# zxuno.net
KiCad netlist of a schematic drawn in Altium Designer
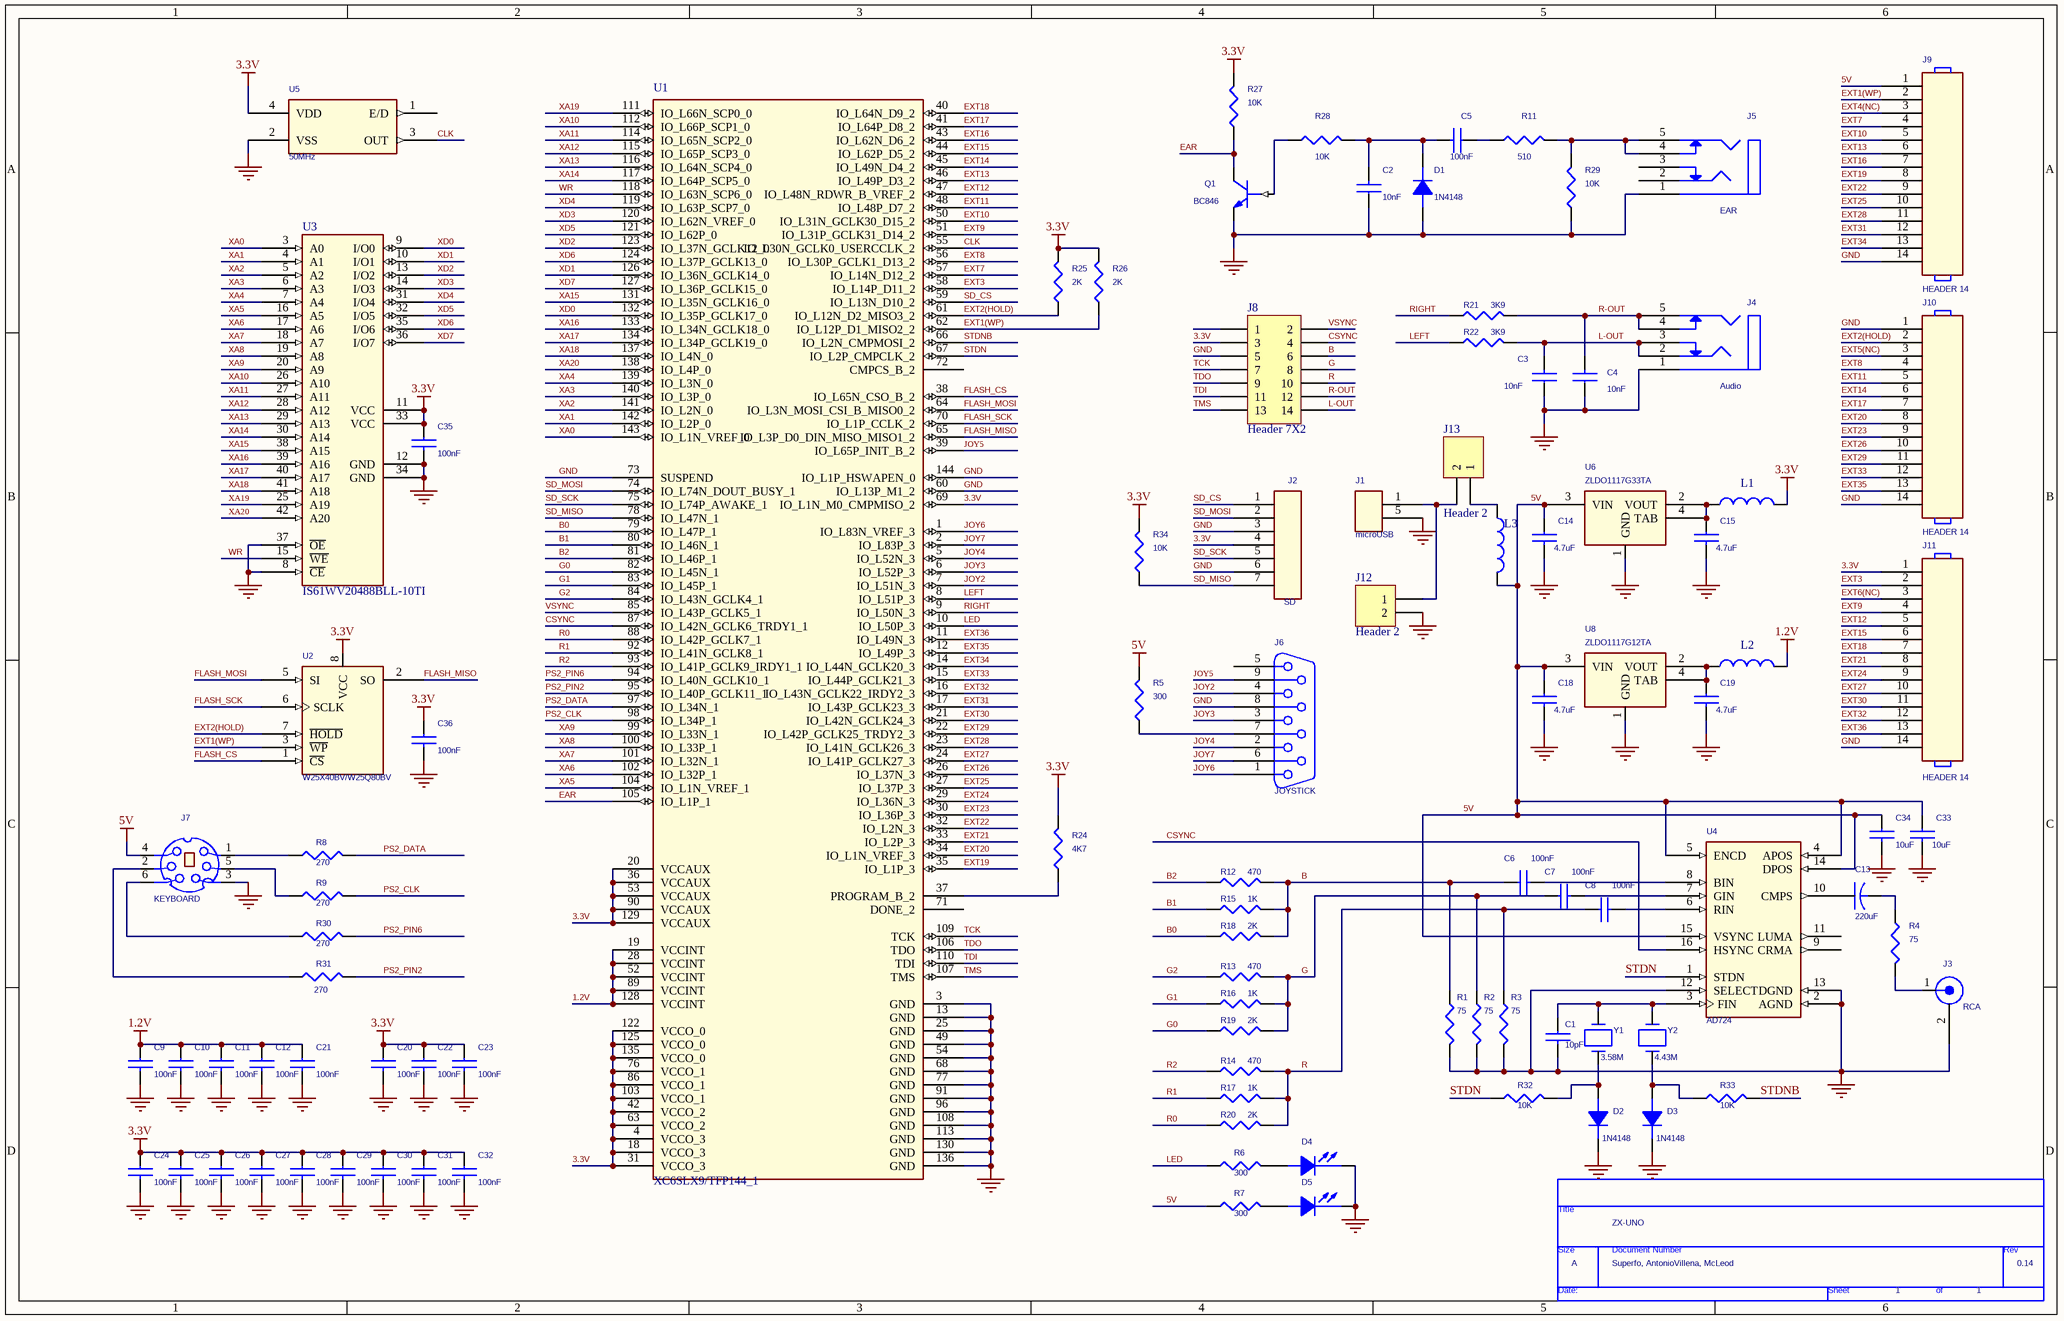
[diagram p0: zxuno.SchDoc]

(export (version "E")
  (design (tool "Eeschema 10.0.6"))
  (components
    (comp (ref "*")
      (value "TitleBlock0")
      (fields
        (field (name "PAGE COUNT") "1")
        (field (name "PAGE NUMBER") "1")
        (field (name "PAGE SIZE") "A")
        (field (name "TITLE") "ZX-UNO")
        (field (name "REVCODE") "0.14")
        (field (name "DOC") "Superfo, AntonioVillena, McLeod")
      )
      (libsource (lib "*") (part "TitleBlock0"))
    )
    (comp (ref "C1") (value "10pF") (libsource (lib "*") (part "CAP NP_Dup1")))
    (comp (ref "C2") (value "10nF") (libsource (lib "*") (part "CAP NP_Dup1")))
    (comp (ref "C3") (value "10nF") (libsource (lib "*") (part "CAP NP_Dup1")))
    (comp (ref "C4") (value "10nF") (libsource (lib "*") (part "CAP NP_Dup1")))
    (comp (ref "C5") (value "100nF") (libsource (lib "*") (part "CAP NP_Dup1")))
    (comp (ref "C6") (value "100nF") (libsource (lib "*") (part "CAP NP_Dup1")))
    (comp (ref "C7") (value "100nF") (libsource (lib "*") (part "CAP NP_Dup1")))
    (comp (ref "C8") (value "100nF") (libsource (lib "*") (part "CAP NP_Dup1")))
    (comp (ref "C9") (value "100nF") (libsource (lib "*") (part "CAP NP")))
    (comp (ref "C10") (value "100nF") (libsource (lib "*") (part "CAP NP")))
    (comp (ref "C11") (value "100nF") (libsource (lib "*") (part "CAP NP")))
    (comp (ref "C12") (value "100nF") (libsource (lib "*") (part "CAP NP")))
    (comp (ref "C13") (value "220uF") (libsource (lib "*") (part "CAP")))
    (comp (ref "C14") (value "4.7uF") (libsource (lib "*") (part "CAP NP")))
    (comp (ref "C15") (value "4.7uF") (libsource (lib "*") (part "CAP NP")))
    (comp (ref "C18") (value "4.7uF") (libsource (lib "*") (part "CAP NP")))
    (comp (ref "C19") (value "4.7uF") (libsource (lib "*") (part "CAP NP")))
    (comp (ref "C20") (value "100nF") (libsource (lib "*") (part "CAP NP")))
    (comp (ref "C21") (value "100nF") (libsource (lib "*") (part "CAP NP")))
    (comp (ref "C22") (value "100nF") (libsource (lib "*") (part "CAP NP")))
    (comp (ref "C23") (value "100nF") (libsource (lib "*") (part "CAP NP")))
    (comp (ref "C24") (value "100nF") (libsource (lib "*") (part "CAP NP")))
    (comp (ref "C25") (value "100nF") (libsource (lib "*") (part "CAP NP")))
    (comp (ref "C26") (value "100nF") (libsource (lib "*") (part "CAP NP")))
    (comp (ref "C27") (value "100nF") (libsource (lib "*") (part "CAP NP")))
    (comp (ref "C28") (value "100nF") (libsource (lib "*") (part "CAP NP")))
    (comp (ref "C29") (value "100nF") (libsource (lib "*") (part "CAP NP")))
    (comp (ref "C30") (value "100nF") (libsource (lib "*") (part "CAP NP")))
    (comp (ref "C31") (value "100nF") (libsource (lib "*") (part "CAP NP")))
    (comp (ref "C32") (value "100nF") (libsource (lib "*") (part "CAP NP")))
    (comp (ref "C33") (value "10uF") (libsource (lib "*") (part "CAP NP")))
    (comp (ref "C34") (value "10uF") (libsource (lib "*") (part "CAP NP")))
    (comp (ref "C35") (value "100nF") (libsource (lib "*") (part "CAP NP")))
    (comp (ref "C36") (value "100nF") (libsource (lib "*") (part "CAP NP")))
    (comp (ref "D1") (value "1N4148") (libsource (lib "*") (part "DIODE")))
    (comp (ref "D2") (value "1N4148") (libsource (lib "*") (part "DIODE")))
    (comp (ref "D3") (value "1N4148") (libsource (lib "*") (part "DIODE")))
    (comp (ref "D4") (value "LED") (libsource (lib "*") (part "LED")))
    (comp (ref "D5") (value "LED") (libsource (lib "*") (part "LED")))
    (comp (ref "J1") (value "microUSB") (libsource (lib "*") (part "CON2_0")))
    (comp (ref "J2") (value "SD") (libsource (lib "*") (part "CON7")))
    (comp (ref "J3") (value "RCA") (libsource (lib "*") (part "RCA JACK")))
    (comp (ref "J4")
      (value "Audio")
      (footprint "AUDIO JACK PSG01538 - duplicate")
      (libsource (lib "*") (part "PHONEJACK STEREO SW_0"))
    )
    (comp (ref "J5") (value "EAR") (libsource (lib "*") (part "PHONEJACK STEREO SW_0")))
    (comp (ref "J6") (value "JOYSTICK") (libsource (lib "*") (part "CONNECTOR DB9")))
    (comp (ref "J7") (value "KEYBOARD") (libsource (lib "*") (part "M-DIN_0")))
    (comp (ref "J8")
      (value "Header 7X2")
      (footprint "HDR2X7")
      (description "Header, 7-Pin, Dual row")
      (fields (field (name "PUBLISHER") "Altium Limited"))
      (libsource (lib "Miscellaneous Connectors") (part "Header 7X2"))
    )
    (comp (ref "J9") (value "HEADER 14") (libsource (lib "*") (part "HEADER 14")))
    (comp (ref "J10") (value "HEADER 14") (libsource (lib "*") (part "HEADER 14")))
    (comp (ref "J11") (value "HEADER 14") (libsource (lib "*") (part "HEADER 14")))
    (comp (ref "J12")
      (value "Header 2")
      (footprint "HDR1X2")
      (description "Header, 2-Pin")
      (fields (field (name "PUBLISHER") "Altium Limited"))
      (libsource (lib "Miscellaneous Connectors") (part "Header 2"))
    )
    (comp (ref "J13")
      (value "Header 2")
      (footprint "HDR1X2")
      (description "Header, 2-Pin")
      (fields (field (name "PUBLISHER") "Altium Limited"))
      (libsource (lib "") (part "Header 2_1"))
    )
    (comp (ref "L1")
      (value "Inductor")
      (footprint "SM/L_0805")
      (fields (field (name "PUBLISHER") "Altium Limited"))
      (libsource (lib "Miscellaneous Devices") (part "Inductor"))
    )
    (comp (ref "L2")
      (value "Inductor")
      (footprint "SM/L_0805")
      (fields (field (name "PUBLISHER") "Altium Limited"))
      (libsource (lib "Miscellaneous Devices") (part "Inductor"))
    )
    (comp (ref "L3")
      (value "Inductor")
      (footprint "SM/L_0805")
      (fields (field (name "PUBLISHER") "Altium Limited"))
      (libsource (lib "Miscellaneous Devices") (part "Inductor"))
    )
    (comp (ref "Q1") (value "BC846") (libsource (lib "*") (part "BC547")))
    (comp (ref "R1") (value "75") (libsource (lib "*") (part "R")))
    (comp (ref "R2") (value "75") (libsource (lib "*") (part "R")))
    (comp (ref "R3") (value "75") (libsource (lib "*") (part "R")))
    (comp (ref "R4") (value "75") (libsource (lib "*") (part "R")))
    (comp (ref "R5") (value "300") (libsource (lib "*") (part "R")))
    (comp (ref "R6") (value "300") (libsource (lib "*") (part "R")))
    (comp (ref "R7") (value "300") (libsource (lib "*") (part "R")))
    (comp (ref "R8") (value "270") (libsource (lib "*") (part "R")))
    (comp (ref "R9") (value "270") (libsource (lib "*") (part "R")))
    (comp (ref "R11") (value "510") (libsource (lib "*") (part "R")))
    (comp (ref "R12") (value "470") (libsource (lib "*") (part "R")))
    (comp (ref "R13") (value "470") (libsource (lib "*") (part "R")))
    (comp (ref "R14") (value "470") (libsource (lib "*") (part "R")))
    (comp (ref "R15") (value "1K") (libsource (lib "*") (part "R")))
    (comp (ref "R16") (value "1K") (libsource (lib "*") (part "R")))
    (comp (ref "R17") (value "1K") (libsource (lib "*") (part "R")))
    (comp (ref "R18") (value "2K") (libsource (lib "*") (part "R")))
    (comp (ref "R19") (value "2K") (libsource (lib "*") (part "R")))
    (comp (ref "R20") (value "2K") (libsource (lib "*") (part "R")))
    (comp (ref "R21") (value "3K9") (libsource (lib "*") (part "R")))
    (comp (ref "R22") (value "3K9") (libsource (lib "*") (part "R")))
    (comp (ref "R24") (value "4K7") (libsource (lib "*") (part "R")))
    (comp (ref "R25") (value "2K") (libsource (lib "*") (part "R")))
    (comp (ref "R26") (value "2K") (libsource (lib "*") (part "R")))
    (comp (ref "R27") (value "10K") (libsource (lib "*") (part "R")))
    (comp (ref "R28") (value "10K") (libsource (lib "*") (part "R")))
    (comp (ref "R29") (value "10K") (libsource (lib "*") (part "R")))
    (comp (ref "R30") (value "270") (libsource (lib "*") (part "R")))
    (comp (ref "R31") (value "270") (libsource (lib "*") (part "R")))
    (comp (ref "R32") (value "10K") (libsource (lib "*") (part "R")))
    (comp (ref "R33") (value "10K") (libsource (lib "*") (part "R")))
    (comp (ref "R34") (value "10K") (libsource (lib "*") (part "R")))
    (comp (ref "U1")
      (value "XC6SLX9/TFP144_1")
      (libsource (lib "ZX_UNO_0_13_Library") (part "XC6SLX9/TFP144_1"))
    )
    (comp (ref "U2") (value "W25X40BV/W25Q80BV") (libsource (lib "*") (part "AT45DB011/SOIC_3")))
    (comp (ref "U3")
      (value "IS61WV20488BLL-10TI")
      (footprint "SOP80P1176-44M")
      (libsource (lib "ZX_UNO_Library") (part "IS61WV20488BLL-10TI"))
    )
    (comp (ref "U4") (value "AD724") (libsource (lib "*") (part "AD724")))
    (comp (ref "U5") (value "50MHz") (libsource (lib "*") (part "CS-403/TO_0")))
    (comp (ref "U6")
      (value "ZLDO1117G33TA")
      (footprint "SM/SOT223")
      (libsource (lib "*") (part "REGULATOR-1_0"))
    )
    (comp (ref "U8")
      (value "ZLDO1117G12TA")
      (footprint "SM/SOT223")
      (libsource (lib "*") (part "REGULATOR-1_0"))
    )
    (comp (ref "Y1") (value "3.58M") (libsource (lib "*") (part "CRYSTAL")))
    (comp (ref "Y2") (value "4.43M") (libsource (lib "*") (part "CRYSTAL")))
  )
  (nets
    (net (code "1") (name "/B") (class "Default")
      (node (ref "C6") (pin "1") (pinfunction "1_1") (pintype "passive"))
      (node (ref "J8") (pin "6") (pinfunction "6_6") (pintype "passive"))
      (node (ref "R1") (pin "1") (pinfunction "1_1") (pintype "passive"))
      (node (ref "R12") (pin "2") (pinfunction "2_2") (pintype "passive"))
      (node (ref "R15") (pin "2") (pinfunction "2_2") (pintype "passive"))
      (node (ref "R18") (pin "2") (pinfunction "2_2") (pintype "passive"))
    )
    (net (code "2") (name "/B0") (class "Default")
      (node (ref "R18") (pin "1") (pinfunction "1_1") (pintype "passive"))
      (node (ref "U1") (pin "79") (pinfunction "IO_L47P_1_79") (pintype "bidirectional"))
    )
    (net (code "3") (name "/B1") (class "Default")
      (node (ref "R15") (pin "1") (pinfunction "1_1") (pintype "passive"))
      (node (ref "U1") (pin "80") (pinfunction "IO_L46N_1_80") (pintype "bidirectional"))
    )
    (net (code "4") (name "/B2") (class "Default")
      (node (ref "R12") (pin "1") (pinfunction "1_1") (pintype "passive"))
      (node (ref "U1") (pin "81") (pinfunction "IO_L46P_1_81") (pintype "bidirectional"))
    )
    (net (code "5") (name "/CLK") (class "Default")
      (node (ref "U1") (pin "55") (pinfunction "IO_L30N_GCLK0_USERCCLK_2_55") (pintype "bidirectional"))
      (node (ref "U5") (pin "3") (pinfunction "OUT_3") (pintype "output"))
    )
    (net (code "6") (name "/CSYNC") (class "Default")
      (node (ref "J8") (pin "4") (pinfunction "4_4") (pintype "passive"))
      (node (ref "U1") (pin "87") (pinfunction "IO_L42N_GCLK6_TRDY1_1_87") (pintype "bidirectional"))
      (node (ref "U4") (pin "16") (pinfunction "HSYNC_16") (pintype "input"))
    )
    (net (code "7") (name "/EAR") (class "Default")
      (node (ref "Q1") (pin "1") (pinfunction "COLLECTOR_1") (pintype "passive"))
      (node (ref "R27") (pin "2") (pinfunction "2_2") (pintype "passive"))
      (node (ref "U1") (pin "105") (pinfunction "IO_L1P_1_105") (pintype "bidirectional"))
    )
    (net (code "8") (name "/EXT1(WP)") (class "Default")
      (node (ref "J9") (pin "2") (pinfunction "2_2") (pintype "passive"))
      (node (ref "R26") (pin "1") (pinfunction "1_1") (pintype "passive"))
      (node (ref "U1") (pin "62") (pinfunction "IO_L12P_D1_MISO2_2_62") (pintype "bidirectional"))
      (node (ref "U2") (pin "3") (pinfunction "~{WP}_3") (pintype "input"))
    )
    (net (code "9") (name "/EXT2(HOLD)") (class "Default")
      (node (ref "J10") (pin "2") (pinfunction "2_2") (pintype "passive"))
      (node (ref "R25") (pin "1") (pinfunction "1_1") (pintype "passive"))
      (node (ref "U1") (pin "61") (pinfunction "IO_L12N_D2_MISO3_2_61") (pintype "bidirectional"))
      (node (ref "U2") (pin "7") (pinfunction "~{HOLD}_7") (pintype "input"))
    )
    (net (code "10") (name "/EXT3") (class "Default")
      (node (ref "J11") (pin "2") (pinfunction "2_2") (pintype "passive"))
      (node (ref "U1") (pin "58") (pinfunction "IO_L14P_D11_2_58") (pintype "bidirectional"))
    )
    (net (code "11") (name "/EXT4(NC)") (class "Default")
      (node (ref "J9") (pin "3") (pinfunction "3_3") (pintype "passive"))
    )
    (net (code "12") (name "/EXT5(NC)") (class "Default")
      (node (ref "J10") (pin "3") (pinfunction "3_3") (pintype "passive"))
    )
    (net (code "13") (name "/EXT6(NC)") (class "Default")
      (node (ref "J11") (pin "3") (pinfunction "3_3") (pintype "passive"))
    )
    (net (code "14") (name "/EXT7") (class "Default")
      (node (ref "J9") (pin "4") (pinfunction "4_4") (pintype "passive"))
      (node (ref "U1") (pin "57") (pinfunction "IO_L14N_D12_2_57") (pintype "bidirectional"))
    )
    (net (code "15") (name "/EXT8") (class "Default")
      (node (ref "J10") (pin "4") (pinfunction "4_4") (pintype "passive"))
      (node (ref "U1") (pin "56") (pinfunction "IO_L30P_GCLK1_D13_2_56") (pintype "bidirectional"))
    )
    (net (code "16") (name "/EXT9") (class "Default")
      (node (ref "J11") (pin "4") (pinfunction "4_4") (pintype "passive"))
      (node (ref "U1") (pin "51") (pinfunction "IO_L31P_GCLK31_D14_2_51") (pintype "bidirectional"))
    )
    (net (code "17") (name "/EXT10") (class "Default")
      (node (ref "J9") (pin "5") (pinfunction "5_5") (pintype "passive"))
      (node (ref "U1") (pin "50") (pinfunction "IO_L31N_GCLK30_D15_2_50") (pintype "bidirectional"))
    )
    (net (code "18") (name "/EXT11") (class "Default")
      (node (ref "J10") (pin "5") (pinfunction "5_5") (pintype "passive"))
      (node (ref "U1") (pin "48") (pinfunction "IO_L48P_D7_2_48") (pintype "bidirectional"))
    )
    (net (code "19") (name "/EXT12") (class "Default")
      (node (ref "J11") (pin "5") (pinfunction "5_5") (pintype "passive"))
      (node (ref "U1") (pin "47") (pinfunction "IO_L48N_RDWR_B_VREF_2_47") (pintype "bidirectional"))
    )
    (net (code "20") (name "/EXT13") (class "Default")
      (node (ref "J9") (pin "6") (pinfunction "6_6") (pintype "passive"))
      (node (ref "U1") (pin "46") (pinfunction "IO_L49P_D3_2_46") (pintype "bidirectional"))
    )
    (net (code "21") (name "/EXT14") (class "Default")
      (node (ref "J10") (pin "6") (pinfunction "6_6") (pintype "passive"))
      (node (ref "U1") (pin "45") (pinfunction "IO_L49N_D4_2_45") (pintype "bidirectional"))
    )
    (net (code "22") (name "/EXT15") (class "Default")
      (node (ref "J11") (pin "6") (pinfunction "6_6") (pintype "passive"))
      (node (ref "U1") (pin "44") (pinfunction "IO_L62P_D5_2_44") (pintype "bidirectional"))
    )
    (net (code "23") (name "/EXT16") (class "Default")
      (node (ref "J9") (pin "7") (pinfunction "7_7") (pintype "passive"))
      (node (ref "U1") (pin "43") (pinfunction "IO_L62N_D6_2_43") (pintype "bidirectional"))
    )
    (net (code "24") (name "/EXT17") (class "Default")
      (node (ref "J10") (pin "7") (pinfunction "7_7") (pintype "passive"))
      (node (ref "U1") (pin "41") (pinfunction "IO_L64P_D8_2_41") (pintype "bidirectional"))
    )
    (net (code "25") (name "/EXT18") (class "Default")
      (node (ref "J11") (pin "7") (pinfunction "7_7") (pintype "passive"))
      (node (ref "U1") (pin "40") (pinfunction "IO_L64N_D9_2_40") (pintype "bidirectional"))
    )
    (net (code "26") (name "/EXT19") (class "Default")
      (node (ref "J9") (pin "8") (pinfunction "8_8") (pintype "passive"))
      (node (ref "U1") (pin "35") (pinfunction "IO_L1P_3_35") (pintype "bidirectional"))
    )
    (net (code "27") (name "/EXT20") (class "Default")
      (node (ref "J10") (pin "8") (pinfunction "8_8") (pintype "passive"))
      (node (ref "U1") (pin "34") (pinfunction "IO_L1N_VREF_3_34") (pintype "bidirectional"))
    )
    (net (code "28") (name "/EXT21") (class "Default")
      (node (ref "J11") (pin "8") (pinfunction "8_8") (pintype "passive"))
      (node (ref "U1") (pin "33") (pinfunction "IO_L2P_3_33") (pintype "bidirectional"))
    )
    (net (code "29") (name "/EXT22") (class "Default")
      (node (ref "J9") (pin "9") (pinfunction "9_9") (pintype "passive"))
      (node (ref "U1") (pin "32") (pinfunction "IO_L2N_3_32") (pintype "bidirectional"))
    )
    (net (code "30") (name "/EXT23") (class "Default")
      (node (ref "J10") (pin "9") (pinfunction "9_9") (pintype "passive"))
      (node (ref "U1") (pin "30") (pinfunction "IO_L36P_3_30") (pintype "bidirectional"))
    )
    (net (code "31") (name "/EXT24") (class "Default")
      (node (ref "J11") (pin "9") (pinfunction "9_9") (pintype "passive"))
      (node (ref "U1") (pin "29") (pinfunction "IO_L36N_3_29") (pintype "bidirectional"))
    )
    (net (code "32") (name "/EXT25") (class "Default")
      (node (ref "J9") (pin "10") (pinfunction "10_10") (pintype "passive"))
      (node (ref "U1") (pin "27") (pinfunction "IO_L37P_3_27") (pintype "bidirectional"))
    )
    (net (code "33") (name "/EXT26") (class "Default")
      (node (ref "J10") (pin "10") (pinfunction "10_10") (pintype "passive"))
      (node (ref "U1") (pin "26") (pinfunction "IO_L37N_3_26") (pintype "bidirectional"))
    )
    (net (code "34") (name "/EXT27") (class "Default")
      (node (ref "J11") (pin "10") (pinfunction "10_10") (pintype "passive"))
      (node (ref "U1") (pin "24") (pinfunction "IO_L41P_GCLK27_3_24") (pintype "bidirectional"))
    )
    (net (code "35") (name "/EXT28") (class "Default")
      (node (ref "J9") (pin "11") (pinfunction "11_11") (pintype "passive"))
      (node (ref "U1") (pin "23") (pinfunction "IO_L41N_GCLK26_3_23") (pintype "bidirectional"))
    )
    (net (code "36") (name "/EXT29") (class "Default")
      (node (ref "J10") (pin "11") (pinfunction "11_11") (pintype "passive"))
      (node (ref "U1") (pin "22") (pinfunction "IO_L42P_GCLK25_TRDY2_3_22") (pintype "bidirectional"))
    )
    (net (code "37") (name "/EXT30") (class "Default")
      (node (ref "J11") (pin "11") (pinfunction "11_11") (pintype "passive"))
      (node (ref "U1") (pin "21") (pinfunction "IO_L42N_GCLK24_3_21") (pintype "bidirectional"))
    )
    (net (code "38") (name "/EXT31") (class "Default")
      (node (ref "J9") (pin "12") (pinfunction "12_12") (pintype "passive"))
      (node (ref "U1") (pin "17") (pinfunction "IO_L43P_GCLK23_3_17") (pintype "bidirectional"))
    )
    (net (code "39") (name "/EXT32") (class "Default")
      (node (ref "J11") (pin "12") (pinfunction "12_12") (pintype "passive"))
      (node (ref "U1") (pin "16") (pinfunction "IO_L43N_GCLK22_IRDY2_3_16") (pintype "bidirectional"))
    )
    (net (code "40") (name "/EXT33") (class "Default")
      (node (ref "J10") (pin "12") (pinfunction "12_12") (pintype "passive"))
      (node (ref "U1") (pin "15") (pinfunction "IO_L44P_GCLK21_3_15") (pintype "bidirectional"))
    )
    (net (code "41") (name "/EXT34") (class "Default")
      (node (ref "J9") (pin "13") (pinfunction "13_13") (pintype "passive"))
      (node (ref "U1") (pin "14") (pinfunction "IO_L44N_GCLK20_3_14") (pintype "bidirectional"))
    )
    (net (code "42") (name "/EXT35") (class "Default")
      (node (ref "J10") (pin "13") (pinfunction "13_13") (pintype "passive"))
      (node (ref "U1") (pin "12") (pinfunction "IO_L49P_3_12") (pintype "bidirectional"))
    )
    (net (code "43") (name "/EXT36") (class "Default")
      (node (ref "J11") (pin "13") (pinfunction "13_13") (pintype "passive"))
      (node (ref "U1") (pin "11") (pinfunction "IO_L49N_3_11") (pintype "bidirectional"))
    )
    (net (code "44") (name "/FLASH_CS") (class "Default")
      (node (ref "U1") (pin "38") (pinfunction "IO_L65N_CSO_B_2_38") (pintype "bidirectional"))
      (node (ref "U2") (pin "1") (pinfunction "~{CS}_1") (pintype "input"))
    )
    (net (code "45") (name "/FLASH_MISO") (class "Default")
      (node (ref "U1") (pin "65") (pinfunction "IO_L3P_D0_DIN_MISO_MISO1_2_65") (pintype "bidirectional"))
      (node (ref "U2") (pin "2") (pinfunction "SO_2") (pintype "tri_state"))
    )
    (net (code "46") (name "/FLASH_MOSI") (class "Default")
      (node (ref "U1") (pin "64") (pinfunction "IO_L3N_MOSI_CSI_B_MISO0_2_64") (pintype "bidirectional"))
      (node (ref "U2") (pin "5") (pinfunction "SI_5") (pintype "input"))
    )
    (net (code "47") (name "/FLASH_SCK") (class "Default")
      (node (ref "U1") (pin "70") (pinfunction "IO_L1P_CCLK_2_70") (pintype "bidirectional"))
      (node (ref "U2") (pin "6") (pinfunction "SCLK_6") (pintype "input"))
    )
    (net (code "48") (name "/G") (class "Default")
      (node (ref "C7") (pin "1") (pinfunction "1_1") (pintype "passive"))
      (node (ref "J8") (pin "8") (pinfunction "8_8") (pintype "passive"))
      (node (ref "R13") (pin "2") (pinfunction "2_2") (pintype "passive"))
      (node (ref "R16") (pin "2") (pinfunction "2_2") (pintype "passive"))
      (node (ref "R19") (pin "2") (pinfunction "2_2") (pintype "passive"))
      (node (ref "R2") (pin "1") (pinfunction "1_1") (pintype "passive"))
    )
    (net (code "49") (name "/G0") (class "Default")
      (node (ref "R19") (pin "1") (pinfunction "1_1") (pintype "passive"))
      (node (ref "U1") (pin "82") (pinfunction "IO_L45N_1_82") (pintype "bidirectional"))
    )
    (net (code "50") (name "/G1") (class "Default")
      (node (ref "R16") (pin "1") (pinfunction "1_1") (pintype "passive"))
      (node (ref "U1") (pin "83") (pinfunction "IO_L45P_1_83") (pintype "bidirectional"))
    )
    (net (code "51") (name "/G2") (class "Default")
      (node (ref "R13") (pin "1") (pinfunction "1_1") (pintype "passive"))
      (node (ref "U1") (pin "84") (pinfunction "IO_L43N_GCLK4_1_84") (pintype "bidirectional"))
    )
    (net (code "52") (name "/JOY2") (class "Default")
      (node (ref "J6") (pin "4") (pinfunction "4_4") (pintype "passive"))
      (node (ref "U1") (pin "7") (pinfunction "IO_L51N_3_7") (pintype "bidirectional"))
    )
    (net (code "53") (name "/JOY3") (class "Default")
      (node (ref "J6") (pin "3") (pinfunction "3_3") (pintype "passive"))
      (node (ref "U1") (pin "6") (pinfunction "IO_L52P_3_6") (pintype "bidirectional"))
    )
    (net (code "54") (name "/JOY4") (class "Default")
      (node (ref "J6") (pin "2") (pinfunction "2_2") (pintype "passive"))
      (node (ref "U1") (pin "5") (pinfunction "IO_L52N_3_5") (pintype "bidirectional"))
    )
    (net (code "55") (name "/JOY5") (class "Default")
      (node (ref "J6") (pin "9") (pinfunction "9_9") (pintype "passive"))
      (node (ref "U1") (pin "39") (pinfunction "IO_L65P_INIT_B_2_39") (pintype "bidirectional"))
    )
    (net (code "56") (name "/JOY6") (class "Default")
      (node (ref "J6") (pin "1") (pinfunction "1_1") (pintype "passive"))
      (node (ref "U1") (pin "1") (pinfunction "IO_L83N_VREF_3_1") (pintype "bidirectional"))
    )
    (net (code "57") (name "/JOY7") (class "Default")
      (node (ref "J6") (pin "6") (pinfunction "6_6") (pintype "passive"))
      (node (ref "U1") (pin "2") (pinfunction "IO_L83P_3_2") (pintype "bidirectional"))
    )
    (net (code "58") (name "/L-OUT") (class "Default")
      (node (ref "C3") (pin "2") (pinfunction "2_2") (pintype "passive"))
      (node (ref "J4") (pin "2") (pinfunction "D_2") (pintype "passive"))
      (node (ref "J4") (pin "3") (pinfunction "C_3") (pintype "passive"))
      (node (ref "J8") (pin "14") (pinfunction "14_14") (pintype "passive"))
      (node (ref "R22") (pin "2") (pinfunction "2_2") (pintype "passive"))
    )
    (net (code "59") (name "/LED") (class "Default")
      (node (ref "R6") (pin "1") (pinfunction "1_1") (pintype "passive"))
      (node (ref "U1") (pin "10") (pinfunction "IO_L50P_3_10") (pintype "bidirectional"))
    )
    (net (code "60") (name "/LEFT") (class "Default")
      (node (ref "R22") (pin "1") (pinfunction "1_1") (pintype "passive"))
      (node (ref "U1") (pin "8") (pinfunction "IO_L51P_3_8") (pintype "bidirectional"))
    )
    (net (code "61") (name "/PS2_CLK") (class "Default")
      (node (ref "R9") (pin "2") (pinfunction "2_2") (pintype "passive"))
      (node (ref "U1") (pin "98") (pinfunction "IO_L34P_1_98") (pintype "bidirectional"))
    )
    (net (code "62") (name "/PS2_DATA") (class "Default")
      (node (ref "R8") (pin "2") (pinfunction "2_2") (pintype "passive"))
      (node (ref "U1") (pin "97") (pinfunction "IO_L34N_1_97") (pintype "bidirectional"))
    )
    (net (code "63") (name "/PS2_PIN2") (class "Default")
      (node (ref "R31") (pin "2") (pinfunction "2_2") (pintype "passive"))
      (node (ref "U1") (pin "95") (pinfunction "IO_L40P_GCLK11_1_95") (pintype "bidirectional"))
    )
    (net (code "64") (name "/PS2_PIN6") (class "Default")
      (node (ref "R30") (pin "2") (pinfunction "2_2") (pintype "passive"))
      (node (ref "U1") (pin "94") (pinfunction "IO_L40N_GCLK10_1_94") (pintype "bidirectional"))
    )
    (net (code "65") (name "/R") (class "Default")
      (node (ref "C8") (pin "1") (pinfunction "1_1") (pintype "passive"))
      (node (ref "J8") (pin "10") (pinfunction "10_10") (pintype "passive"))
      (node (ref "R14") (pin "2") (pinfunction "2_2") (pintype "passive"))
      (node (ref "R17") (pin "2") (pinfunction "2_2") (pintype "passive"))
      (node (ref "R20") (pin "2") (pinfunction "2_2") (pintype "passive"))
      (node (ref "R3") (pin "1") (pinfunction "1_1") (pintype "passive"))
    )
    (net (code "66") (name "/R-OUT") (class "Default")
      (node (ref "C4") (pin "2") (pinfunction "2_2") (pintype "passive"))
      (node (ref "J4") (pin "4") (pinfunction "B_4") (pintype "passive"))
      (node (ref "J4") (pin "5") (pinfunction "A_5") (pintype "passive"))
      (node (ref "J8") (pin "12") (pinfunction "12_12") (pintype "passive"))
      (node (ref "R21") (pin "2") (pinfunction "2_2") (pintype "passive"))
    )
    (net (code "67") (name "/R0") (class "Default")
      (node (ref "R20") (pin "1") (pinfunction "1_1") (pintype "passive"))
      (node (ref "U1") (pin "88") (pinfunction "IO_L42P_GCLK7_1_88") (pintype "bidirectional"))
    )
    (net (code "68") (name "/R1") (class "Default")
      (node (ref "R17") (pin "1") (pinfunction "1_1") (pintype "passive"))
      (node (ref "U1") (pin "92") (pinfunction "IO_L41N_GCLK8_1_92") (pintype "bidirectional"))
    )
    (net (code "69") (name "/R2") (class "Default")
      (node (ref "R14") (pin "1") (pinfunction "1_1") (pintype "passive"))
      (node (ref "U1") (pin "93") (pinfunction "IO_L41P_GCLK9_IRDY1_1_93") (pintype "bidirectional"))
    )
    (net (code "70") (name "/RIGHT") (class "Default")
      (node (ref "R21") (pin "1") (pinfunction "1_1") (pintype "passive"))
      (node (ref "U1") (pin "9") (pinfunction "IO_L50N_3_9") (pintype "bidirectional"))
    )
    (net (code "71") (name "/SD_CS") (class "Default")
      (node (ref "J2") (pin "1") (pinfunction "1_1") (pintype "passive"))
      (node (ref "U1") (pin "59") (pinfunction "IO_L13N_D10_2_59") (pintype "bidirectional"))
    )
    (net (code "72") (name "/SD_MISO") (class "Default")
      (node (ref "J2") (pin "7") (pinfunction "7_7") (pintype "passive"))
      (node (ref "R34") (pin "1") (pinfunction "1_1") (pintype "passive"))
      (node (ref "U1") (pin "78") (pinfunction "IO_L47N_1_78") (pintype "bidirectional"))
    )
    (net (code "73") (name "/SD_MOSI") (class "Default")
      (node (ref "J2") (pin "2") (pinfunction "2_2") (pintype "passive"))
      (node (ref "U1") (pin "74") (pinfunction "IO_L74N_DOUT_BUSY_1_74") (pintype "bidirectional"))
    )
    (net (code "74") (name "/SD_SCK") (class "Default")
      (node (ref "J2") (pin "5") (pinfunction "5_5") (pintype "passive"))
      (node (ref "U1") (pin "75") (pinfunction "IO_L74P_AWAKE_1_75") (pintype "bidirectional"))
    )
    (net (code "75") (name "/STDN") (class "Default")
      (node (ref "R32") (pin "1") (pinfunction "1_1") (pintype "passive"))
      (node (ref "U1") (pin "67") (pinfunction "IO_L2P_CMPCLK_2_67") (pintype "bidirectional"))
      (node (ref "U4") (pin "1") (pinfunction "STDN_1") (pintype "input"))
    )
    (net (code "76") (name "/STDNB") (class "Default")
      (node (ref "R33") (pin "2") (pinfunction "2_2") (pintype "passive"))
      (node (ref "U1") (pin "66") (pinfunction "IO_L2N_CMPMOSI_2_66") (pintype "bidirectional"))
    )
    (net (code "77") (name "/TCK") (class "Default")
      (node (ref "J8") (pin "7") (pinfunction "7_7") (pintype "passive"))
      (node (ref "U1") (pin "109") (pinfunction "TCK_109") (pintype "bidirectional"))
    )
    (net (code "78") (name "/TDI") (class "Default")
      (node (ref "J8") (pin "11") (pinfunction "11_11") (pintype "passive"))
      (node (ref "U1") (pin "110") (pinfunction "TDI_110") (pintype "bidirectional"))
    )
    (net (code "79") (name "/TDO") (class "Default")
      (node (ref "J8") (pin "9") (pinfunction "9_9") (pintype "passive"))
      (node (ref "U1") (pin "106") (pinfunction "TDO_106") (pintype "bidirectional"))
    )
    (net (code "80") (name "/TMS") (class "Default")
      (node (ref "J8") (pin "13") (pinfunction "13_13") (pintype "passive"))
      (node (ref "U1") (pin "107") (pinfunction "TMS_107") (pintype "bidirectional"))
    )
    (net (code "81") (name "/VSYNC") (class "Default")
      (node (ref "J8") (pin "2") (pinfunction "2_2") (pintype "passive"))
      (node (ref "U1") (pin "85") (pinfunction "IO_L43P_GCLK5_1_85") (pintype "bidirectional"))
    )
    (net (code "82") (name "/WR") (class "Default")
      (node (ref "U1") (pin "118") (pinfunction "IO_L63N_SCP6_0_118") (pintype "bidirectional"))
      (node (ref "U3") (pin "15") (pinfunction "~{WE}_15") (pintype "input"))
    )
    (net (code "83") (name "/XA0") (class "Default")
      (node (ref "U1") (pin "143") (pinfunction "IO_L1N_VREF_0_143") (pintype "bidirectional"))
      (node (ref "U3") (pin "3") (pinfunction "A0_3") (pintype "input"))
    )
    (net (code "84") (name "/XA1") (class "Default")
      (node (ref "U1") (pin "142") (pinfunction "IO_L2P_0_142") (pintype "bidirectional"))
      (node (ref "U3") (pin "4") (pinfunction "A1_4") (pintype "input"))
    )
    (net (code "85") (name "/XA2") (class "Default")
      (node (ref "U1") (pin "141") (pinfunction "IO_L2N_0_141") (pintype "bidirectional"))
      (node (ref "U3") (pin "5") (pinfunction "A2_5") (pintype "input"))
    )
    (net (code "86") (name "/XA3") (class "Default")
      (node (ref "U1") (pin "140") (pinfunction "IO_L3P_0_140") (pintype "bidirectional"))
      (node (ref "U3") (pin "6") (pinfunction "A3_6") (pintype "input"))
    )
    (net (code "87") (name "/XA4") (class "Default")
      (node (ref "U1") (pin "139") (pinfunction "IO_L3N_0_139") (pintype "bidirectional"))
      (node (ref "U3") (pin "7") (pinfunction "A4_7") (pintype "input"))
    )
    (net (code "88") (name "/XA5") (class "Default")
      (node (ref "U1") (pin "104") (pinfunction "IO_L1N_VREF_1_104") (pintype "bidirectional"))
      (node (ref "U3") (pin "16") (pinfunction "A5_16") (pintype "input"))
    )
    (net (code "89") (name "/XA6") (class "Default")
      (node (ref "U1") (pin "102") (pinfunction "IO_L32P_1_102") (pintype "bidirectional"))
      (node (ref "U3") (pin "17") (pinfunction "A6_17") (pintype "input"))
    )
    (net (code "90") (name "/XA7") (class "Default")
      (node (ref "U1") (pin "101") (pinfunction "IO_L32N_1_101") (pintype "bidirectional"))
      (node (ref "U3") (pin "18") (pinfunction "A7_18") (pintype "input"))
    )
    (net (code "91") (name "/XA8") (class "Default")
      (node (ref "U1") (pin "100") (pinfunction "IO_L33P_1_100") (pintype "bidirectional"))
      (node (ref "U3") (pin "19") (pinfunction "A8_19") (pintype "input"))
    )
    (net (code "92") (name "/XA9") (class "Default")
      (node (ref "U1") (pin "99") (pinfunction "IO_L33N_1_99") (pintype "bidirectional"))
      (node (ref "U3") (pin "20") (pinfunction "A9_20") (pintype "input"))
    )
    (net (code "93") (name "/XA10") (class "Default")
      (node (ref "U1") (pin "112") (pinfunction "IO_L66P_SCP1_0_112") (pintype "bidirectional"))
      (node (ref "U3") (pin "26") (pinfunction "A10_26") (pintype "input"))
    )
    (net (code "94") (name "/XA11") (class "Default")
      (node (ref "U1") (pin "114") (pinfunction "IO_L65N_SCP2_0_114") (pintype "bidirectional"))
      (node (ref "U3") (pin "27") (pinfunction "A11_27") (pintype "input"))
    )
    (net (code "95") (name "/XA12") (class "Default")
      (node (ref "U1") (pin "115") (pinfunction "IO_L65P_SCP3_0_115") (pintype "bidirectional"))
      (node (ref "U3") (pin "28") (pinfunction "A12_28") (pintype "input"))
    )
    (net (code "96") (name "/XA13") (class "Default")
      (node (ref "U1") (pin "116") (pinfunction "IO_L64N_SCP4_0_116") (pintype "bidirectional"))
      (node (ref "U3") (pin "29") (pinfunction "A13_29") (pintype "input"))
    )
    (net (code "97") (name "/XA14") (class "Default")
      (node (ref "U1") (pin "117") (pinfunction "IO_L64P_SCP5_0_117") (pintype "bidirectional"))
      (node (ref "U3") (pin "30") (pinfunction "A14_30") (pintype "input"))
    )
    (net (code "98") (name "/XA15") (class "Default")
      (node (ref "U1") (pin "131") (pinfunction "IO_L35N_GCLK16_0_131") (pintype "bidirectional"))
      (node (ref "U3") (pin "38") (pinfunction "A15_38") (pintype "input"))
    )
    (net (code "99") (name "/XA16") (class "Default")
      (node (ref "U1") (pin "133") (pinfunction "IO_L34N_GCLK18_0_133") (pintype "bidirectional"))
      (node (ref "U3") (pin "39") (pinfunction "A16_39") (pintype "input"))
    )
    (net (code "100") (name "/XA17") (class "Default")
      (node (ref "U1") (pin "134") (pinfunction "IO_L34P_GCLK19_0_134") (pintype "bidirectional"))
      (node (ref "U3") (pin "40") (pinfunction "A17_40") (pintype "input"))
    )
    (net (code "101") (name "/XA18") (class "Default")
      (node (ref "U1") (pin "137") (pinfunction "IO_L4N_0_137") (pintype "bidirectional"))
      (node (ref "U3") (pin "41") (pinfunction "A18_41") (pintype "input"))
    )
    (net (code "102") (name "/XA19") (class "Default")
      (node (ref "U1") (pin "111") (pinfunction "IO_L66N_SCP0_0_111") (pintype "bidirectional"))
      (node (ref "U3") (pin "25") (pinfunction "A19_25") (pintype "input"))
    )
    (net (code "103") (name "/XA20") (class "Default")
      (node (ref "U1") (pin "138") (pinfunction "IO_L4P_0_138") (pintype "bidirectional"))
      (node (ref "U3") (pin "42") (pinfunction "A20_42") (pintype "input"))
    )
    (net (code "104") (name "/XD0") (class "Default")
      (node (ref "U1") (pin "132") (pinfunction "IO_L35P_GCLK17_0_132") (pintype "bidirectional"))
      (node (ref "U3") (pin "9") (pinfunction "I/O0_9") (pintype "bidirectional"))
    )
    (net (code "105") (name "/XD1") (class "Default")
      (node (ref "U1") (pin "126") (pinfunction "IO_L36N_GCLK14_0_126") (pintype "bidirectional"))
      (node (ref "U3") (pin "10") (pinfunction "I/O1_10") (pintype "bidirectional"))
    )
    (net (code "106") (name "/XD2") (class "Default")
      (node (ref "U1") (pin "123") (pinfunction "IO_L37N_GCLK12_0_123") (pintype "bidirectional"))
      (node (ref "U3") (pin "13") (pinfunction "I/O2_13") (pintype "bidirectional"))
    )
    (net (code "107") (name "/XD3") (class "Default")
      (node (ref "U1") (pin "120") (pinfunction "IO_L62N_VREF_0_120") (pintype "bidirectional"))
      (node (ref "U3") (pin "14") (pinfunction "I/O3_14") (pintype "bidirectional"))
    )
    (net (code "108") (name "/XD4") (class "Default")
      (node (ref "U1") (pin "119") (pinfunction "IO_L63P_SCP7_0_119") (pintype "bidirectional"))
      (node (ref "U3") (pin "31") (pinfunction "I/O4_31") (pintype "bidirectional"))
    )
    (net (code "109") (name "/XD5") (class "Default")
      (node (ref "U1") (pin "121") (pinfunction "IO_L62P_0_121") (pintype "bidirectional"))
      (node (ref "U3") (pin "32") (pinfunction "I/O5_32") (pintype "bidirectional"))
    )
    (net (code "110") (name "/XD6") (class "Default")
      (node (ref "U1") (pin "124") (pinfunction "IO_L37P_GCLK13_0_124") (pintype "bidirectional"))
      (node (ref "U3") (pin "35") (pinfunction "I/O6_35") (pintype "bidirectional"))
    )
    (net (code "111") (name "/XD7") (class "Default")
      (node (ref "U1") (pin "127") (pinfunction "IO_L36P_GCLK15_0_127") (pintype "bidirectional"))
      (node (ref "U3") (pin "36") (pinfunction "I/O7_36") (pintype "bidirectional"))
    )
    (net (code "112") (name "1.2V") (class "Default")
      (node (ref "C10") (pin "1") (pinfunction "1_1") (pintype "passive"))
      (node (ref "C11") (pin "1") (pinfunction "1_1") (pintype "passive"))
      (node (ref "C12") (pin "1") (pinfunction "1_1") (pintype "passive"))
      (node (ref "C21") (pin "1") (pinfunction "1_1") (pintype "passive"))
      (node (ref "C9") (pin "1") (pinfunction "1_1") (pintype "passive"))
      (node (ref "L2") (pin "2") (pinfunction "2_2") (pintype "passive"))
      (node (ref "U1") (pin "128") (pinfunction "VCCINT_128") (pintype "passive"))
      (node (ref "U1") (pin "19") (pinfunction "VCCINT_19") (pintype "passive"))
      (node (ref "U1") (pin "28") (pinfunction "VCCINT_28") (pintype "passive"))
      (node (ref "U1") (pin "52") (pinfunction "VCCINT_52") (pintype "passive"))
      (node (ref "U1") (pin "89") (pinfunction "VCCINT_89") (pintype "passive"))
    )
    (net (code "113") (name "3.3V") (class "Default")
      (node (ref "C20") (pin "1") (pinfunction "1_1") (pintype "passive"))
      (node (ref "C22") (pin "1") (pinfunction "1_1") (pintype "passive"))
      (node (ref "C23") (pin "1") (pinfunction "1_1") (pintype "passive"))
      (node (ref "C24") (pin "1") (pinfunction "1_1") (pintype "passive"))
      (node (ref "C25") (pin "1") (pinfunction "1_1") (pintype "passive"))
      (node (ref "C26") (pin "1") (pinfunction "1_1") (pintype "passive"))
      (node (ref "C27") (pin "1") (pinfunction "1_1") (pintype "passive"))
      (node (ref "C28") (pin "1") (pinfunction "1_1") (pintype "passive"))
      (node (ref "C29") (pin "1") (pinfunction "1_1") (pintype "passive"))
      (node (ref "C30") (pin "1") (pinfunction "1_1") (pintype "passive"))
      (node (ref "C31") (pin "1") (pinfunction "1_1") (pintype "passive"))
      (node (ref "C32") (pin "1") (pinfunction "1_1") (pintype "passive"))
      (node (ref "C35") (pin "1") (pinfunction "1_1") (pintype "passive"))
      (node (ref "C36") (pin "1") (pinfunction "1_1") (pintype "passive"))
      (node (ref "J11") (pin "1") (pinfunction "1_1") (pintype "passive"))
      (node (ref "J2") (pin "4") (pinfunction "4_4") (pintype "passive"))
      (node (ref "J8") (pin "3") (pinfunction "3_3") (pintype "passive"))
      (node (ref "L1") (pin "2") (pinfunction "2_2") (pintype "passive"))
      (node (ref "R24") (pin "2") (pinfunction "2_2") (pintype "passive"))
      (node (ref "R25") (pin "2") (pinfunction "2_2") (pintype "passive"))
      (node (ref "R26") (pin "2") (pinfunction "2_2") (pintype "passive"))
      (node (ref "R27") (pin "1") (pinfunction "1_1") (pintype "passive"))
      (node (ref "R34") (pin "2") (pinfunction "2_2") (pintype "passive"))
      (node (ref "U1") (pin "103") (pinfunction "VCCO_1_103") (pintype "passive"))
      (node (ref "U1") (pin "122") (pinfunction "VCCO_0_122") (pintype "passive"))
      (node (ref "U1") (pin "125") (pinfunction "VCCO_0_125") (pintype "passive"))
      (node (ref "U1") (pin "129") (pinfunction "VCCAUX_129") (pintype "passive"))
      (node (ref "U1") (pin "135") (pinfunction "VCCO_0_135") (pintype "passive"))
      (node (ref "U1") (pin "18") (pinfunction "VCCO_3_18") (pintype "passive"))
      (node (ref "U1") (pin "20") (pinfunction "VCCAUX_20") (pintype "passive"))
      (node (ref "U1") (pin "31") (pinfunction "VCCO_3_31") (pintype "passive"))
      (node (ref "U1") (pin "36") (pinfunction "VCCAUX_36") (pintype "passive"))
      (node (ref "U1") (pin "4") (pinfunction "VCCO_3_4") (pintype "passive"))
      (node (ref "U1") (pin "42") (pinfunction "VCCO_2_42") (pintype "passive"))
      (node (ref "U1") (pin "53") (pinfunction "VCCAUX_53") (pintype "passive"))
      (node (ref "U1") (pin "63") (pinfunction "VCCO_2_63") (pintype "passive"))
      (node (ref "U1") (pin "69") (pinfunction "IO_L1N_M0_CMPMISO_2_69") (pintype "bidirectional"))
      (node (ref "U1") (pin "76") (pinfunction "VCCO_1_76") (pintype "passive"))
      (node (ref "U1") (pin "86") (pinfunction "VCCO_1_86") (pintype "passive"))
      (node (ref "U1") (pin "90") (pinfunction "VCCAUX_90") (pintype "passive"))
      (node (ref "U2") (pin "8") (pinfunction "VCC_8") (pintype "power_in"))
      (node (ref "U3") (pin "11") (pinfunction "VCC_11") (pintype "power_in"))
      (node (ref "U3") (pin "33") (pinfunction "VCC_33") (pintype "power_in"))
      (node (ref "U5") (pin "4") (pinfunction "VDD_4") (pintype "power_in"))
    )
    (net (code "114") (name "5V") (class "Default")
      (node (ref "C14") (pin "1") (pinfunction "1_1") (pintype "passive"))
      (node (ref "C18") (pin "1") (pinfunction "1_1") (pintype "passive"))
      (node (ref "C33") (pin "1") (pinfunction "1_1") (pintype "passive"))
      (node (ref "C34") (pin "1") (pinfunction "1_1") (pintype "passive"))
      (node (ref "J7") (pin "4") (pinfunction "4_4") (pintype "passive"))
      (node (ref "J9") (pin "1") (pinfunction "1_1") (pintype "passive"))
      (node (ref "L3") (pin "2") (pinfunction "2_2") (pintype "passive"))
      (node (ref "R5") (pin "2") (pinfunction "2_2") (pintype "passive"))
      (node (ref "R7") (pin "1") (pinfunction "1_1") (pintype "passive"))
      (node (ref "U4") (pin "14") (pinfunction "DPOS_14") (pintype "input"))
      (node (ref "U4") (pin "15") (pinfunction "VSYNC_15") (pintype "input"))
      (node (ref "U4") (pin "4") (pinfunction "APOS_4") (pintype "input"))
      (node (ref "U4") (pin "5") (pinfunction "ENCD_5") (pintype "input"))
      (node (ref "U6") (pin "3") (pinfunction "VIN_3") (pintype "power_in"))
      (node (ref "U8") (pin "3") (pinfunction "VIN_3") (pintype "power_in"))
    )
    (net (code "115") (name "GND") (class "Default")
      (node (ref "C1") (pin "2") (pinfunction "2_2") (pintype "passive"))
      (node (ref "C10") (pin "2") (pinfunction "2_2") (pintype "passive"))
      (node (ref "C11") (pin "2") (pinfunction "2_2") (pintype "passive"))
      (node (ref "C12") (pin "2") (pinfunction "2_2") (pintype "passive"))
      (node (ref "C14") (pin "2") (pinfunction "2_2") (pintype "passive"))
      (node (ref "C15") (pin "2") (pinfunction "2_2") (pintype "passive"))
      (node (ref "C18") (pin "2") (pinfunction "2_2") (pintype "passive"))
      (node (ref "C19") (pin "2") (pinfunction "2_2") (pintype "passive"))
      (node (ref "C2") (pin "1") (pinfunction "1_1") (pintype "passive"))
      (node (ref "C20") (pin "2") (pinfunction "2_2") (pintype "passive"))
      (node (ref "C21") (pin "2") (pinfunction "2_2") (pintype "passive"))
      (node (ref "C22") (pin "2") (pinfunction "2_2") (pintype "passive"))
      (node (ref "C23") (pin "2") (pinfunction "2_2") (pintype "passive"))
      (node (ref "C24") (pin "2") (pinfunction "2_2") (pintype "passive"))
      (node (ref "C25") (pin "2") (pinfunction "2_2") (pintype "passive"))
      (node (ref "C26") (pin "2") (pinfunction "2_2") (pintype "passive"))
      (node (ref "C27") (pin "2") (pinfunction "2_2") (pintype "passive"))
      (node (ref "C28") (pin "2") (pinfunction "2_2") (pintype "passive"))
      (node (ref "C29") (pin "2") (pinfunction "2_2") (pintype "passive"))
      (node (ref "C3") (pin "1") (pinfunction "1_1") (pintype "passive"))
      (node (ref "C30") (pin "2") (pinfunction "2_2") (pintype "passive"))
      (node (ref "C31") (pin "2") (pinfunction "2_2") (pintype "passive"))
      (node (ref "C32") (pin "2") (pinfunction "2_2") (pintype "passive"))
      (node (ref "C33") (pin "2") (pinfunction "2_2") (pintype "passive"))
      (node (ref "C34") (pin "2") (pinfunction "2_2") (pintype "passive"))
      (node (ref "C35") (pin "2") (pinfunction "2_2") (pintype "passive"))
      (node (ref "C36") (pin "2") (pinfunction "2_2") (pintype "passive"))
      (node (ref "C4") (pin "1") (pinfunction "1_1") (pintype "passive"))
      (node (ref "C9") (pin "2") (pinfunction "2_2") (pintype "passive"))
      (node (ref "D1") (pin "1") (pinfunction "A_1") (pintype "passive"))
      (node (ref "D2") (pin "2") (pinfunction "K_2") (pintype "passive"))
      (node (ref "D3") (pin "2") (pinfunction "K_2") (pintype "passive"))
      (node (ref "D4") (pin "2") (pinfunction "CATHODE_2") (pintype "passive"))
      (node (ref "D5") (pin "2") (pinfunction "CATHODE_2") (pintype "passive"))
      (node (ref "J1") (pin "5") (pinfunction "5_5") (pintype "passive"))
      (node (ref "J10") (pin "1") (pinfunction "1_1") (pintype "passive"))
      (node (ref "J10") (pin "14") (pinfunction "14_14") (pintype "passive"))
      (node (ref "J11") (pin "14") (pinfunction "14_14") (pintype "passive"))
      (node (ref "J12") (pin "2") (pinfunction "2_2") (pintype "passive"))
      (node (ref "J2") (pin "3") (pinfunction "3_3") (pintype "passive"))
      (node (ref "J2") (pin "6") (pinfunction "6_6") (pintype "passive"))
      (node (ref "J3") (pin "2") (pinfunction "SHIELD_2") (pintype "passive"))
      (node (ref "J4") (pin "1") (pinfunction "E_1") (pintype "passive"))
      (node (ref "J5") (pin "1") (pinfunction "E_1") (pintype "passive"))
      (node (ref "J6") (pin "8") (pinfunction "8_8") (pintype "passive"))
      (node (ref "J7") (pin "3") (pinfunction "3_3") (pintype "passive"))
      (node (ref "J7") (pin "M1") (pinfunction "GND_M1") (pintype "power_in"))
      (node (ref "J7") (pin "M2") (pinfunction "GND_M2") (pintype "power_in"))
      (node (ref "J7") (pin "M3") (pinfunction "GND_M3") (pintype "power_in"))
      (node (ref "J8") (pin "5") (pinfunction "5_5") (pintype "passive"))
      (node (ref "J9") (pin "14") (pinfunction "14_14") (pintype "passive"))
      (node (ref "Q1") (pin "3") (pinfunction "EMITTER_3") (pintype "passive"))
      (node (ref "R1") (pin "2") (pinfunction "2_2") (pintype "passive"))
      (node (ref "R2") (pin "2") (pinfunction "2_2") (pintype "passive"))
      (node (ref "R29") (pin "2") (pinfunction "2_2") (pintype "passive"))
      (node (ref "R3") (pin "2") (pinfunction "2_2") (pintype "passive"))
      (node (ref "U1") (pin "108") (pinfunction "GND_108") (pintype "power_in"))
      (node (ref "U1") (pin "113") (pinfunction "GND_113") (pintype "power_in"))
      (node (ref "U1") (pin "13") (pinfunction "GND_13") (pintype "passive"))
      (node (ref "U1") (pin "130") (pinfunction "GND_130") (pintype "passive"))
      (node (ref "U1") (pin "136") (pinfunction "GND_136") (pintype "passive"))
      (node (ref "U1") (pin "144") (pinfunction "IO_L1P_HSWAPEN_0_144") (pintype "bidirectional"))
      (node (ref "U1") (pin "25") (pinfunction "GND_25") (pintype "passive"))
      (node (ref "U1") (pin "3") (pinfunction "GND_3") (pintype "passive"))
      (node (ref "U1") (pin "49") (pinfunction "GND_49") (pintype "passive"))
      (node (ref "U1") (pin "54") (pinfunction "GND_54") (pintype "passive"))
      (node (ref "U1") (pin "60") (pinfunction "IO_L13P_M1_2_60") (pintype "bidirectional"))
      (node (ref "U1") (pin "68") (pinfunction "GND_68") (pintype "passive"))
      (node (ref "U1") (pin "73") (pinfunction "SUSPEND_73") (pintype "passive"))
      (node (ref "U1") (pin "77") (pinfunction "GND_77") (pintype "power_in"))
      (node (ref "U1") (pin "91") (pinfunction "GND_91") (pintype "power_in"))
      (node (ref "U1") (pin "96") (pinfunction "GND_96") (pintype "power_in"))
      (node (ref "U2") (pin "4") (pinfunction "GND_4") (pintype "power_in"))
      (node (ref "U3") (pin "12") (pinfunction "GND_12") (pintype "power_in"))
      (node (ref "U3") (pin "34") (pinfunction "GND_34") (pintype "power_in"))
      (node (ref "U3") (pin "37") (pinfunction "~{OE}_37") (pintype "input"))
      (node (ref "U3") (pin "8") (pinfunction "~{CE}_8") (pintype "input"))
      (node (ref "U4") (pin "12") (pinfunction "SELECT_12") (pintype "input"))
      (node (ref "U4") (pin "13") (pinfunction "DGND_13") (pintype "input"))
      (node (ref "U4") (pin "2") (pinfunction "AGND_2") (pintype "input"))
      (node (ref "U5") (pin "2") (pinfunction "VSS_2") (pintype "passive"))
      (node (ref "U6") (pin "1") (pinfunction "GND_1") (pintype "power_in"))
      (node (ref "U8") (pin "1") (pinfunction "GND_1") (pintype "power_in"))
    )
    (net (code "116") (name "Net-(C5-Pad1)") (class "Default")
      (node (ref "C5") (pin "1") (pinfunction "1_1") (pintype "passive"))
      (node (ref "R11") (pin "2") (pinfunction "2_2") (pintype "passive"))
    )
    (net (code "117") (name "Net-(C13-Pad2)") (class "Default")
      (node (ref "C13") (pin "2") (pinfunction "2_2") (pintype "passive"))
      (node (ref "R4") (pin "1") (pinfunction "1_1") (pintype "passive"))
    )
    (net (code "118") (name "Net-(D1-K)") (class "Default")
      (node (ref "C2") (pin "2") (pinfunction "2_2") (pintype "passive"))
      (node (ref "C5") (pin "2") (pinfunction "2_2") (pintype "passive"))
      (node (ref "D1") (pin "2") (pinfunction "K_2") (pintype "passive"))
      (node (ref "R28") (pin "1") (pinfunction "1_1") (pintype "passive"))
    )
    (net (code "119") (name "Net-(D2-A)") (class "Default")
      (node (ref "D2") (pin "1") (pinfunction "A_1") (pintype "passive"))
      (node (ref "R32") (pin "2") (pinfunction "2_2") (pintype "passive"))
      (node (ref "Y1") (pin "2") (pinfunction "2_2") (pintype "passive"))
    )
    (net (code "120") (name "Net-(D3-A)") (class "Default")
      (node (ref "D3") (pin "1") (pinfunction "A_1") (pintype "passive"))
      (node (ref "R33") (pin "1") (pinfunction "1_1") (pintype "passive"))
      (node (ref "Y2") (pin "2") (pinfunction "2_2") (pintype "passive"))
    )
    (net (code "121") (name "Net-(D4-ANODE)") (class "Default")
      (node (ref "D4") (pin "1") (pinfunction "ANODE_1") (pintype "passive"))
      (node (ref "R6") (pin "2") (pinfunction "2_2") (pintype "passive"))
    )
    (net (code "122") (name "Net-(D5-ANODE)") (class "Default")
      (node (ref "D5") (pin "1") (pinfunction "ANODE_1") (pintype "passive"))
      (node (ref "R7") (pin "2") (pinfunction "2_2") (pintype "passive"))
    )
    (net (code "123") (name "Net-(J1-Pad1)") (class "Default")
      (node (ref "J1") (pin "1") (pinfunction "1_1") (pintype "passive"))
      (node (ref "J12") (pin "1") (pinfunction "1_1") (pintype "passive"))
      (node (ref "J13") (pin "2") (pinfunction "2_2") (pintype "passive"))
    )
    (net (code "124") (name "Net-(J3-CENTER)") (class "Default")
      (node (ref "J3") (pin "1") (pinfunction "CENTER_1") (pintype "passive"))
      (node (ref "R4") (pin "2") (pinfunction "2_2") (pintype "passive"))
    )
    (net (code "125") (name "Net-(J5-A)") (class "Default")
      (node (ref "J5") (pin "4") (pinfunction "B_4") (pintype "passive"))
      (node (ref "J5") (pin "5") (pinfunction "A_5") (pintype "passive"))
      (node (ref "R11") (pin "1") (pinfunction "1_1") (pintype "passive"))
      (node (ref "R29") (pin "1") (pinfunction "1_1") (pintype "passive"))
    )
    (net (code "126") (name "Net-(J6-Pad7)") (class "Default")
      (node (ref "J6") (pin "7") (pinfunction "7_7") (pintype "passive"))
      (node (ref "R5") (pin "1") (pinfunction "1_1") (pintype "passive"))
    )
    (net (code "127") (name "Net-(J7-Pad1)") (class "Default")
      (node (ref "J7") (pin "1") (pinfunction "1_1") (pintype "passive"))
      (node (ref "R8") (pin "1") (pinfunction "1_1") (pintype "passive"))
    )
    (net (code "128") (name "Net-(J7-Pad2)") (class "Default")
      (node (ref "J7") (pin "2") (pinfunction "2_2") (pintype "passive"))
      (node (ref "R31") (pin "1") (pinfunction "1_1") (pintype "passive"))
    )
    (net (code "129") (name "Net-(J7-Pad5)") (class "Default")
      (node (ref "J7") (pin "5") (pinfunction "5_5") (pintype "passive"))
      (node (ref "R9") (pin "1") (pinfunction "1_1") (pintype "passive"))
    )
    (net (code "130") (name "Net-(J7-Pad6)") (class "Default")
      (node (ref "J7") (pin "6") (pinfunction "6_6") (pintype "passive"))
      (node (ref "R30") (pin "1") (pinfunction "1_1") (pintype "passive"))
    )
    (net (code "131") (name "Net-(J13-Pad1)") (class "Default")
      (node (ref "J13") (pin "1") (pinfunction "1_1") (pintype "passive"))
      (node (ref "L3") (pin "1") (pinfunction "1_1") (pintype "passive"))
    )
    (net (code "132") (name "Net-(Q1-BASE)") (class "Default")
      (node (ref "Q1") (pin "2") (pinfunction "BASE_2") (pintype "input"))
      (node (ref "R28") (pin "2") (pinfunction "2_2") (pintype "passive"))
    )
    (net (code "133") (name "Net-(U1-PROGRAM_B_2)") (class "Default")
      (node (ref "R24") (pin "1") (pinfunction "1_1") (pintype "passive"))
      (node (ref "U1") (pin "37") (pinfunction "PROGRAM_B_2_37") (pintype "passive"))
    )
    (net (code "134") (name "Net-(U4-BIN)") (class "Default")
      (node (ref "C6") (pin "2") (pinfunction "2_2") (pintype "passive"))
      (node (ref "U4") (pin "8") (pinfunction "BIN_8") (pintype "input"))
    )
    (net (code "135") (name "Net-(U4-CMPS)") (class "Default")
      (node (ref "C13") (pin "1") (pinfunction "1_1") (pintype "passive"))
      (node (ref "U4") (pin "10") (pinfunction "CMPS_10") (pintype "output"))
    )
    (net (code "136") (name "Net-(U4-FIN)") (class "Default")
      (node (ref "C1") (pin "1") (pinfunction "1_1") (pintype "passive"))
      (node (ref "U4") (pin "3") (pinfunction "FIN_3") (pintype "input"))
      (node (ref "Y1") (pin "1") (pinfunction "1_1") (pintype "passive"))
      (node (ref "Y2") (pin "1") (pinfunction "1_1") (pintype "passive"))
    )
    (net (code "137") (name "Net-(U4-GIN)") (class "Default")
      (node (ref "C7") (pin "2") (pinfunction "2_2") (pintype "passive"))
      (node (ref "U4") (pin "7") (pinfunction "GIN_7") (pintype "input"))
    )
    (net (code "138") (name "Net-(U4-RIN)") (class "Default")
      (node (ref "C8") (pin "2") (pinfunction "2_2") (pintype "passive"))
      (node (ref "U4") (pin "6") (pinfunction "RIN_6") (pintype "input"))
    )
    (net (code "139") (name "Net-(U6-TAB)") (class "Default")
      (node (ref "C15") (pin "1") (pinfunction "1_1") (pintype "passive"))
      (node (ref "L1") (pin "1") (pinfunction "1_1") (pintype "passive"))
      (node (ref "U6") (pin "2") (pinfunction "VOUT_2") (pintype "power_in"))
      (node (ref "U6") (pin "4") (pinfunction "TAB_4") (pintype "passive"))
    )
    (net (code "140") (name "Net-(U8-TAB)") (class "Default")
      (node (ref "C19") (pin "1") (pinfunction "1_1") (pintype "passive"))
      (node (ref "L2") (pin "1") (pinfunction "1_1") (pintype "passive"))
      (node (ref "U8") (pin "2") (pinfunction "VOUT_2") (pintype "power_in"))
      (node (ref "U8") (pin "4") (pinfunction "TAB_4") (pintype "passive"))
    )
    (net (code "141") (name "unconnected-(J5-C-Pad3)") (class "Default")
      (node (ref "J5") (pin "3") (pinfunction "C_3") (pintype "passive"))
    )
    (net (code "142") (name "unconnected-(J5-D-Pad2)") (class "Default")
      (node (ref "J5") (pin "2") (pinfunction "D_2") (pintype "passive"))
    )
    (net (code "143") (name "unconnected-(J6-Pad5)") (class "Default")
      (node (ref "J6") (pin "5") (pinfunction "5_5") (pintype "passive"))
    )
    (net (code "144") (name "unconnected-(J8-Pad1)") (class "Default")
      (node (ref "J8") (pin "1") (pinfunction "1_1") (pintype "passive"))
    )
    (net (code "145") (name "unconnected-(U1-CMPCS_B_2-Pad72)") (class "Default")
      (node (ref "U1") (pin "72") (pinfunction "CMPCS_B_2_72") (pintype "passive"))
    )
    (net (code "146") (name "unconnected-(U1-DONE_2-Pad71)") (class "Default")
      (node (ref "U1") (pin "71") (pinfunction "DONE_2_71") (pintype "passive"))
    )
    (net (code "147") (name "unconnected-(U4-CRMA-Pad9)") (class "Default")
      (node (ref "U4") (pin "9") (pinfunction "CRMA_9") (pintype "output"))
    )
    (net (code "148") (name "unconnected-(U4-LUMA-Pad11)") (class "Default")
      (node (ref "U4") (pin "11") (pinfunction "LUMA_11") (pintype "output"))
    )
    (net (code "149") (name "unconnected-(U5-E{slash}D-Pad1)") (class "Default")
      (node (ref "U5") (pin "1") (pinfunction "E/D_1") (pintype "output"))
    )
  )
)
